# w5500.net
KiCad netlist of a schematic drawn in Altium Designer
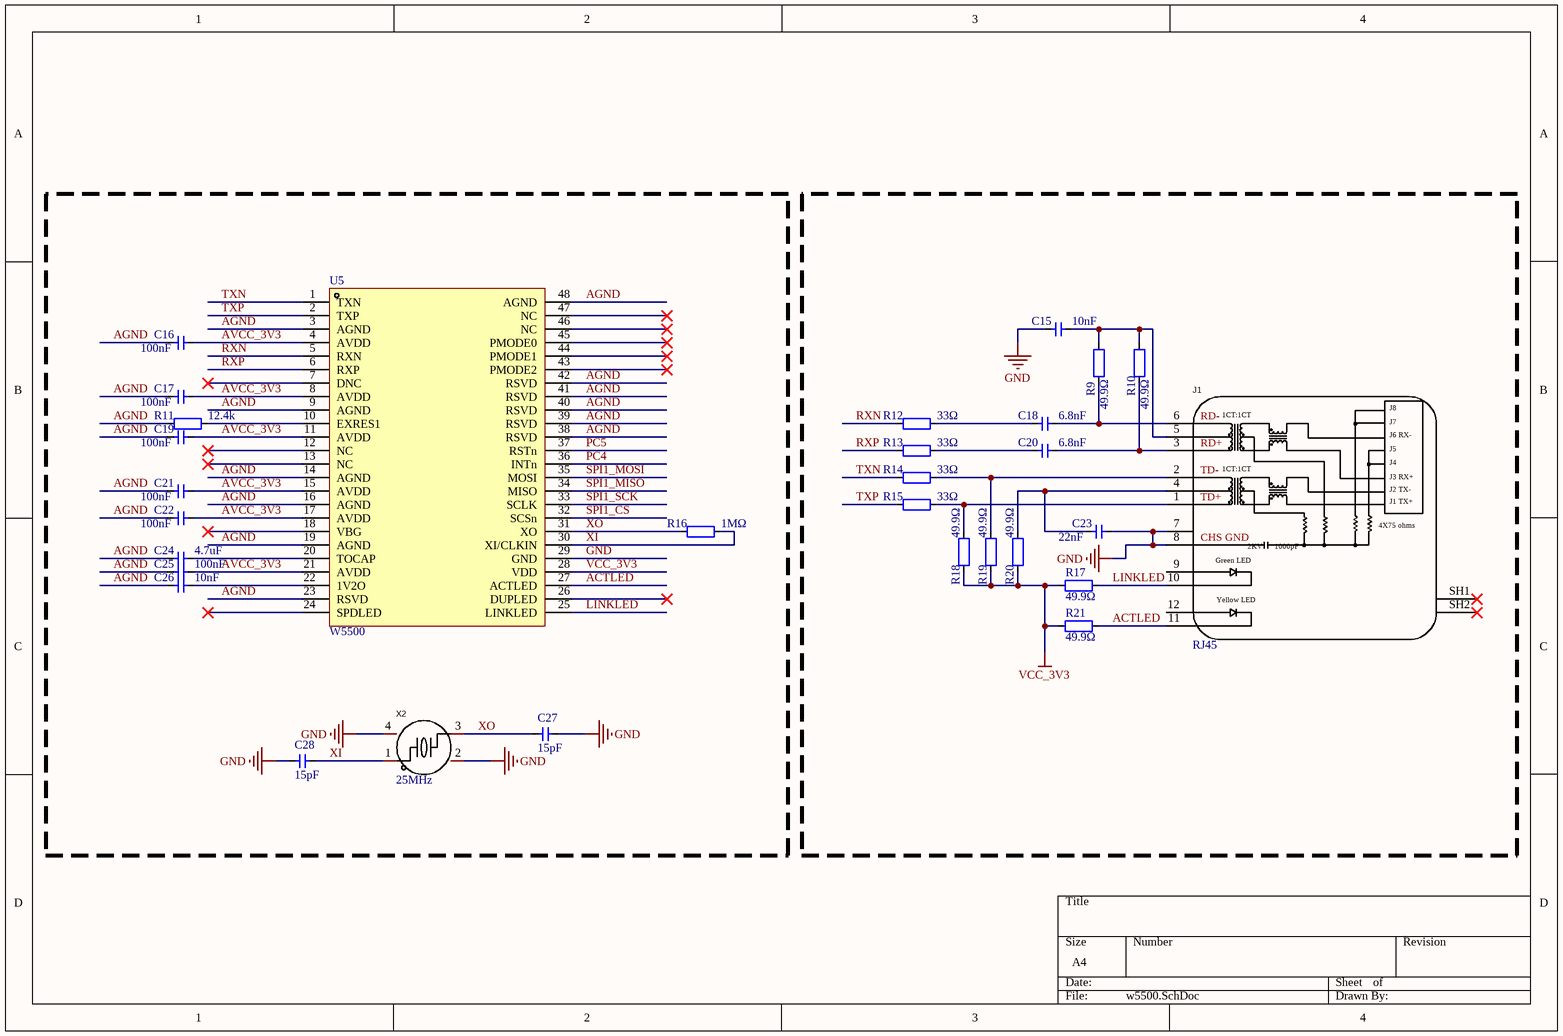
[diagram p0: w5500.SchDoc]

(export (version "E")
  (design (tool "Eeschema 10.0.6"))
  (components
    (comp (ref "C15") (value "10nF") (footprint "C0603") (libsource (lib "vesc6") (part "C0603")))
    (comp (ref "C16") (value "100nF") (footprint "C0603") (libsource (lib "vesc6") (part "C0603")))
    (comp (ref "C17") (value "100nF") (footprint "C0603") (libsource (lib "vesc6") (part "C0603")))
    (comp (ref "C18") (value "6.8nF") (footprint "C0603") (libsource (lib "vesc6") (part "C0603")))
    (comp (ref "C19") (value "100nF") (footprint "C0603") (libsource (lib "vesc6") (part "C0603")))
    (comp (ref "C20") (value "6.8nF") (footprint "C0603") (libsource (lib "vesc6") (part "C0603")))
    (comp (ref "C21") (value "100nF") (footprint "C0603") (libsource (lib "vesc6") (part "C0603")))
    (comp (ref "C22") (value "100nF") (footprint "C0603") (libsource (lib "vesc6") (part "C0603")))
    (comp (ref "C23") (value "22nF") (footprint "C0603") (libsource (lib "vesc6") (part "C0603")))
    (comp (ref "C24") (value "4.7uF") (footprint "C0603") (libsource (lib "vesc6") (part "C0603")))
    (comp (ref "C25") (value "100nF") (footprint "C0603") (libsource (lib "vesc6") (part "C0603")))
    (comp (ref "C26") (value "10nF") (footprint "C0603") (libsource (lib "vesc6") (part "C0603")))
    (comp (ref "C27") (value "15pF") (footprint "C0603") (libsource (lib "vesc6") (part "C0603")))
    (comp (ref "C28") (value "15pF") (footprint "C0603") (libsource (lib "vesc6") (part "C0603")))
    (comp (ref "J1")
      (value "RJ45")
      (footprint "RJ45-TH_HR911105A")
      (fields (field (name "MANUFACTURER") "HANRUN(汉仁)") (field (name "MANUFACTURER PART") "HR911105A"))
      (libsource (lib "Connector") (part "RJ45"))
    )
    (comp (ref "R9") (value "49.9Ω") (footprint "R0603") (libsource (lib "") (part "R0603_2")))
    (comp (ref "R10") (value "49.9Ω") (footprint "R0603") (libsource (lib "") (part "R0603_2")))
    (comp (ref "R11") (value "12.4k") (footprint "R0603") (libsource (lib "") (part "R0603_1")))
    (comp (ref "R12") (value "33Ω") (footprint "R0603") (libsource (lib "") (part "R0603_1")))
    (comp (ref "R13") (value "33Ω") (footprint "R0603") (libsource (lib "") (part "R0603_1")))
    (comp (ref "R14") (value "33Ω") (footprint "R0603") (libsource (lib "") (part "R0603_1")))
    (comp (ref "R15") (value "33Ω") (footprint "R0603") (libsource (lib "") (part "R0603_1")))
    (comp (ref "R16") (value "1MΩ") (footprint "R0603") (libsource (lib "") (part "R0603_1")))
    (comp (ref "R17") (value "49.9Ω") (footprint "R0603") (libsource (lib "vesc6") (part "R0603")))
    (comp (ref "R18") (value "49.9Ω") (footprint "R0603") (libsource (lib "") (part "R0603_3")))
    (comp (ref "R19") (value "49.9Ω") (footprint "R0603") (libsource (lib "") (part "R0603_3")))
    (comp (ref "R20") (value "49.9Ω") (footprint "R0603") (libsource (lib "") (part "R0603_3")))
    (comp (ref "R21") (value "49.9Ω") (footprint "R0603") (libsource (lib "vesc6") (part "R0603")))
    (comp (ref "U5")
      (value "W5500")
      (footprint "LQFP-48_L7.0-W7.0-P0.50-LS9.0-BL")
      (libsource (lib "IC") (part "W5500"))
    )
    (comp (ref "X2")
      (value "25MHz")
      (footprint "CRYSTAL-SMD_4P-L3.2-W2.5-BL-1")
      (fields
        (field (name "MANUFACTURER") "CJ(江苏长电/长晶)")
        (field (name "MANUFACTURER PART") "CJ13-080001210C30")
      )
      (libsource (lib "vesc6") (part "8Mhz"))
    )
  )
  (nets
    (net (code "1") (name "/ACTLED") (class "Default")
      (node (ref "J1") (pin "11") (pintype "passive"))
      (node (ref "R21") (pin "1") (pinfunction "1_1") (pintype "passive"))
      (node (ref "U5") (pin "27") (pinfunction "ACTLED_27") (pintype "passive"))
    )
    (net (code "2") (name "/AGND") (class "Default")
      (node (ref "C16") (pin "1") (pinfunction "1_1") (pintype "passive"))
      (node (ref "C17") (pin "1") (pinfunction "1_1") (pintype "passive"))
      (node (ref "C19") (pin "1") (pinfunction "1_1") (pintype "passive"))
      (node (ref "C21") (pin "1") (pinfunction "1_1") (pintype "passive"))
      (node (ref "C22") (pin "1") (pinfunction "1_1") (pintype "passive"))
      (node (ref "C24") (pin "1") (pinfunction "1_1") (pintype "passive"))
      (node (ref "C25") (pin "1") (pinfunction "1_1") (pintype "passive"))
      (node (ref "C26") (pin "1") (pinfunction "1_1") (pintype "passive"))
      (node (ref "R11") (pin "1") (pinfunction "1_1") (pintype "passive"))
      (node (ref "U5") (pin "14") (pinfunction "AGND_14") (pintype "passive"))
      (node (ref "U5") (pin "16") (pinfunction "AGND_16") (pintype "passive"))
      (node (ref "U5") (pin "19") (pinfunction "AGND_19") (pintype "passive"))
      (node (ref "U5") (pin "23") (pinfunction "RSVD_23") (pintype "passive"))
      (node (ref "U5") (pin "3") (pinfunction "AGND_3") (pintype "passive"))
      (node (ref "U5") (pin "38") (pinfunction "RSVD_38") (pintype "passive"))
      (node (ref "U5") (pin "39") (pinfunction "RSVD_39") (pintype "passive"))
      (node (ref "U5") (pin "40") (pinfunction "RSVD_40") (pintype "passive"))
      (node (ref "U5") (pin "41") (pinfunction "RSVD_41") (pintype "passive"))
      (node (ref "U5") (pin "42") (pinfunction "RSVD_42") (pintype "passive"))
      (node (ref "U5") (pin "48") (pinfunction "AGND_48") (pintype "passive"))
      (node (ref "U5") (pin "9") (pinfunction "AGND_9") (pintype "passive"))
    )
    (net (code "3") (name "/AVCC_3V3") (class "Default")
      (node (ref "C16") (pin "2") (pinfunction "2_2") (pintype "passive"))
      (node (ref "C17") (pin "2") (pinfunction "2_2") (pintype "passive"))
      (node (ref "C19") (pin "2") (pinfunction "2_2") (pintype "passive"))
      (node (ref "C21") (pin "2") (pinfunction "2_2") (pintype "passive"))
      (node (ref "C22") (pin "2") (pinfunction "2_2") (pintype "passive"))
      (node (ref "C25") (pin "2") (pinfunction "2_2") (pintype "passive"))
      (node (ref "U5") (pin "11") (pinfunction "AVDD_11") (pintype "passive"))
      (node (ref "U5") (pin "15") (pinfunction "AVDD_15") (pintype "passive"))
      (node (ref "U5") (pin "17") (pinfunction "AVDD_17") (pintype "passive"))
      (node (ref "U5") (pin "21") (pinfunction "AVDD_21") (pintype "passive"))
      (node (ref "U5") (pin "4") (pinfunction "AVDD_4") (pintype "passive"))
      (node (ref "U5") (pin "8") (pinfunction "AVDD_8") (pintype "passive"))
    )
    (net (code "4") (name "/LINKLED") (class "Default")
      (node (ref "J1") (pin "10") (pintype "passive"))
      (node (ref "R17") (pin "1") (pinfunction "1_1") (pintype "passive"))
      (node (ref "U5") (pin "25") (pinfunction "LINKLED_25") (pintype "passive"))
    )
    (net (code "5") (name "/PC4") (class "Default")
      (node (ref "U5") (pin "36") (pinfunction "INTn_36") (pintype "passive"))
    )
    (net (code "6") (name "/PC5") (class "Default")
      (node (ref "U5") (pin "37") (pinfunction "RSTn_37") (pintype "passive"))
    )
    (net (code "7") (name "/RXN") (class "Default")
      (node (ref "R12") (pin "1") (pinfunction "1_1") (pintype "passive"))
      (node (ref "U5") (pin "5") (pinfunction "RXN_5") (pintype "passive"))
    )
    (net (code "8") (name "/RXP") (class "Default")
      (node (ref "R13") (pin "1") (pinfunction "1_1") (pintype "passive"))
      (node (ref "U5") (pin "6") (pinfunction "RXP_6") (pintype "passive"))
    )
    (net (code "9") (name "/SPI1_CS") (class "Default")
      (node (ref "U5") (pin "32") (pinfunction "SCSn_32") (pintype "passive"))
    )
    (net (code "10") (name "/SPI1_MISO") (class "Default")
      (node (ref "U5") (pin "34") (pinfunction "MISO_34") (pintype "passive"))
    )
    (net (code "11") (name "/SPI1_MOSI") (class "Default")
      (node (ref "U5") (pin "35") (pinfunction "MOSI_35") (pintype "passive"))
    )
    (net (code "12") (name "/SPI1_SCK") (class "Default")
      (node (ref "U5") (pin "33") (pinfunction "SCLK_33") (pintype "passive"))
    )
    (net (code "13") (name "/TXN") (class "Default")
      (node (ref "R14") (pin "1") (pinfunction "1_1") (pintype "passive"))
      (node (ref "U5") (pin "1") (pinfunction "TXN_1") (pintype "passive"))
    )
    (net (code "14") (name "/TXP") (class "Default")
      (node (ref "R15") (pin "1") (pinfunction "1_1") (pintype "passive"))
      (node (ref "U5") (pin "2") (pinfunction "TXP_2") (pintype "passive"))
    )
    (net (code "15") (name "/XI") (class "Default")
      (node (ref "C28") (pin "2") (pinfunction "2_2") (pintype "passive"))
      (node (ref "R16") (pin "2") (pinfunction "2_2") (pintype "passive"))
      (node (ref "U5") (pin "30") (pinfunction "XI/CLKIN_30") (pintype "passive"))
      (node (ref "X2") (pin "1") (pinfunction "1_1") (pintype "passive"))
    )
    (net (code "16") (name "/XO") (class "Default")
      (node (ref "C27") (pin "1") (pinfunction "1_1") (pintype "passive"))
      (node (ref "R16") (pin "1") (pinfunction "1_1") (pintype "passive"))
      (node (ref "U5") (pin "31") (pinfunction "XO_31") (pintype "passive"))
      (node (ref "X2") (pin "3") (pinfunction "3_3") (pintype "passive"))
    )
    (net (code "17") (name "GND") (class "Default")
      (node (ref "C15") (pin "1") (pinfunction "1_1") (pintype "passive"))
      (node (ref "C23") (pin "2") (pinfunction "2_2") (pintype "passive"))
      (node (ref "C27") (pin "2") (pinfunction "2_2") (pintype "passive"))
      (node (ref "C28") (pin "1") (pinfunction "1_1") (pintype "passive"))
      (node (ref "J1") (pin "7") (pintype "passive"))
      (node (ref "J1") (pin "8") (pintype "passive"))
      (node (ref "U5") (pin "29") (pinfunction "GND_29") (pintype "passive"))
      (node (ref "X2") (pin "2") (pinfunction "GND_2") (pintype "passive"))
      (node (ref "X2") (pin "4") (pinfunction "GND_4") (pintype "passive"))
    )
    (net (code "18") (name "Net-(C15-Pad2)") (class "Default")
      (node (ref "C15") (pin "2") (pinfunction "2_2") (pintype "passive"))
      (node (ref "J1") (pin "5") (pintype "passive"))
      (node (ref "R10") (pin "2") (pinfunction "2_2") (pintype "passive"))
      (node (ref "R9") (pin "2") (pinfunction "2_2") (pintype "passive"))
    )
    (net (code "19") (name "Net-(C18-Pad1)") (class "Default")
      (node (ref "C18") (pin "1") (pinfunction "1_1") (pintype "passive"))
      (node (ref "R12") (pin "2") (pinfunction "2_2") (pintype "passive"))
    )
    (net (code "20") (name "Net-(C18-Pad2)") (class "Default")
      (node (ref "C18") (pin "2") (pinfunction "2_2") (pintype "passive"))
      (node (ref "J1") (pin "6") (pintype "passive"))
      (node (ref "R9") (pin "1") (pinfunction "1_1") (pintype "passive"))
    )
    (net (code "21") (name "Net-(C20-Pad1)") (class "Default")
      (node (ref "C20") (pin "1") (pinfunction "1_1") (pintype "passive"))
      (node (ref "R13") (pin "2") (pinfunction "2_2") (pintype "passive"))
    )
    (net (code "22") (name "Net-(C20-Pad2)") (class "Default")
      (node (ref "C20") (pin "2") (pinfunction "2_2") (pintype "passive"))
      (node (ref "J1") (pin "3") (pintype "passive"))
      (node (ref "R10") (pin "1") (pinfunction "1_1") (pintype "passive"))
    )
    (net (code "23") (name "Net-(C23-Pad1)") (class "Default")
      (node (ref "C23") (pin "1") (pinfunction "1_1") (pintype "passive"))
      (node (ref "J1") (pin "4") (pintype "passive"))
      (node (ref "R20") (pin "1") (pinfunction "1_1") (pintype "passive"))
    )
    (net (code "24") (name "Net-(J1-Pad1)") (class "Default")
      (node (ref "J1") (pin "1") (pintype "passive"))
      (node (ref "R15") (pin "2") (pinfunction "2_2") (pintype "passive"))
      (node (ref "R18") (pin "1") (pinfunction "1_1") (pintype "passive"))
    )
    (net (code "25") (name "Net-(J1-Pad2)") (class "Default")
      (node (ref "J1") (pin "2") (pintype "passive"))
      (node (ref "R14") (pin "2") (pinfunction "2_2") (pintype "passive"))
      (node (ref "R19") (pin "1") (pinfunction "1_1") (pintype "passive"))
    )
    (net (code "26") (name "Net-(U5-1V2O)") (class "Default")
      (node (ref "C26") (pin "2") (pinfunction "2_2") (pintype "passive"))
      (node (ref "U5") (pin "22") (pinfunction "1V2O_22") (pintype "passive"))
    )
    (net (code "27") (name "Net-(U5-EXRES1)") (class "Default")
      (node (ref "R11") (pin "2") (pinfunction "2_2") (pintype "passive"))
      (node (ref "U5") (pin "10") (pinfunction "EXRES1_10") (pintype "passive"))
    )
    (net (code "28") (name "Net-(U5-TOCAP)") (class "Default")
      (node (ref "C24") (pin "2") (pinfunction "2_2") (pintype "passive"))
      (node (ref "U5") (pin "20") (pinfunction "TOCAP_20") (pintype "passive"))
    )
    (net (code "29") (name "VCC_3V3") (class "Default")
      (node (ref "R17") (pin "2") (pinfunction "2_2") (pintype "passive"))
      (node (ref "R18") (pin "2") (pinfunction "2_2") (pintype "passive"))
      (node (ref "R19") (pin "2") (pinfunction "2_2") (pintype "passive"))
      (node (ref "R20") (pin "2") (pinfunction "2_2") (pintype "passive"))
      (node (ref "R21") (pin "2") (pinfunction "2_2") (pintype "passive"))
      (node (ref "U5") (pin "28") (pinfunction "VDD_28") (pintype "passive"))
    )
    (net (code "30") (name "unconnected-(J1-Pad9)") (class "Default")
      (node (ref "J1") (pin "9") (pintype "passive"))
    )
    (net (code "31") (name "unconnected-(J1-Pad12)") (class "Default")
      (node (ref "J1") (pin "12") (pintype "passive"))
    )
    (net (code "32") (name "unconnected-(J1-PadSH1)") (class "Default")
      (node (ref "J1") (pin "SH1") (pintype "passive+no_connect"))
    )
    (net (code "33") (name "unconnected-(J1-PadSH2)") (class "Default")
      (node (ref "J1") (pin "SH2") (pintype "passive+no_connect"))
    )
    (net (code "34") (name "unconnected-(U5-DNC-Pad7)") (class "Default")
      (node (ref "U5") (pin "7") (pinfunction "DNC_7") (pintype "passive+no_connect"))
    )
    (net (code "35") (name "unconnected-(U5-DUPLED-Pad26)") (class "Default")
      (node (ref "U5") (pin "26") (pinfunction "DUPLED_26") (pintype "passive+no_connect"))
    )
    (net (code "36") (name "unconnected-(U5-NC-Pad12)") (class "Default")
      (node (ref "U5") (pin "12") (pinfunction "NC_12") (pintype "passive+no_connect"))
    )
    (net (code "37") (name "unconnected-(U5-NC-Pad13)") (class "Default")
      (node (ref "U5") (pin "13") (pinfunction "NC_13") (pintype "passive+no_connect"))
    )
    (net (code "38") (name "unconnected-(U5-NC-Pad46)") (class "Default")
      (node (ref "U5") (pin "46") (pinfunction "NC_46") (pintype "passive+no_connect"))
    )
    (net (code "39") (name "unconnected-(U5-NC-Pad47)") (class "Default")
      (node (ref "U5") (pin "47") (pinfunction "NC_47") (pintype "passive+no_connect"))
    )
    (net (code "40") (name "unconnected-(U5-PMODE0-Pad45)") (class "Default")
      (node (ref "U5") (pin "45") (pinfunction "PMODE0_45") (pintype "passive+no_connect"))
    )
    (net (code "41") (name "unconnected-(U5-PMODE1-Pad44)") (class "Default")
      (node (ref "U5") (pin "44") (pinfunction "PMODE1_44") (pintype "passive+no_connect"))
    )
    (net (code "42") (name "unconnected-(U5-PMODE2-Pad43)") (class "Default")
      (node (ref "U5") (pin "43") (pinfunction "PMODE2_43") (pintype "passive+no_connect"))
    )
    (net (code "43") (name "unconnected-(U5-SPDLED-Pad24)") (class "Default")
      (node (ref "U5") (pin "24") (pinfunction "SPDLED_24") (pintype "passive+no_connect"))
    )
    (net (code "44") (name "unconnected-(U5-VBG-Pad18)") (class "Default")
      (node (ref "U5") (pin "18") (pinfunction "VBG_18") (pintype "passive+no_connect"))
    )
  )
)
